# Adafruit_Feather_M0_Adalogger.net
KiCad netlist of a schematic drawn in EAGLE
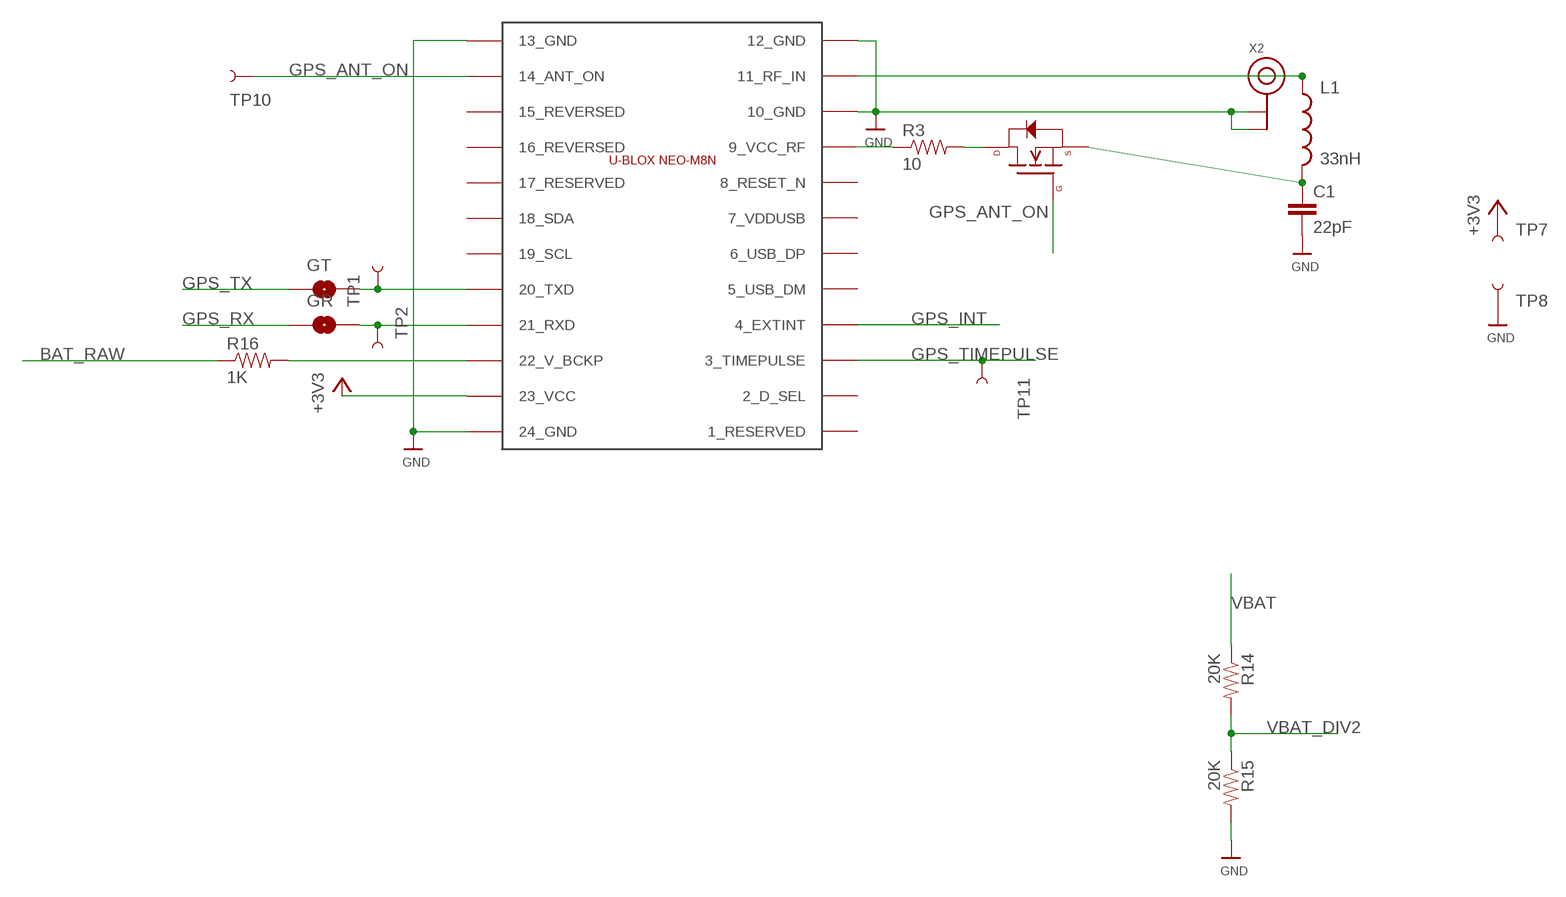
[diagram p0: schematic, sheet 1, part 1 of 2]
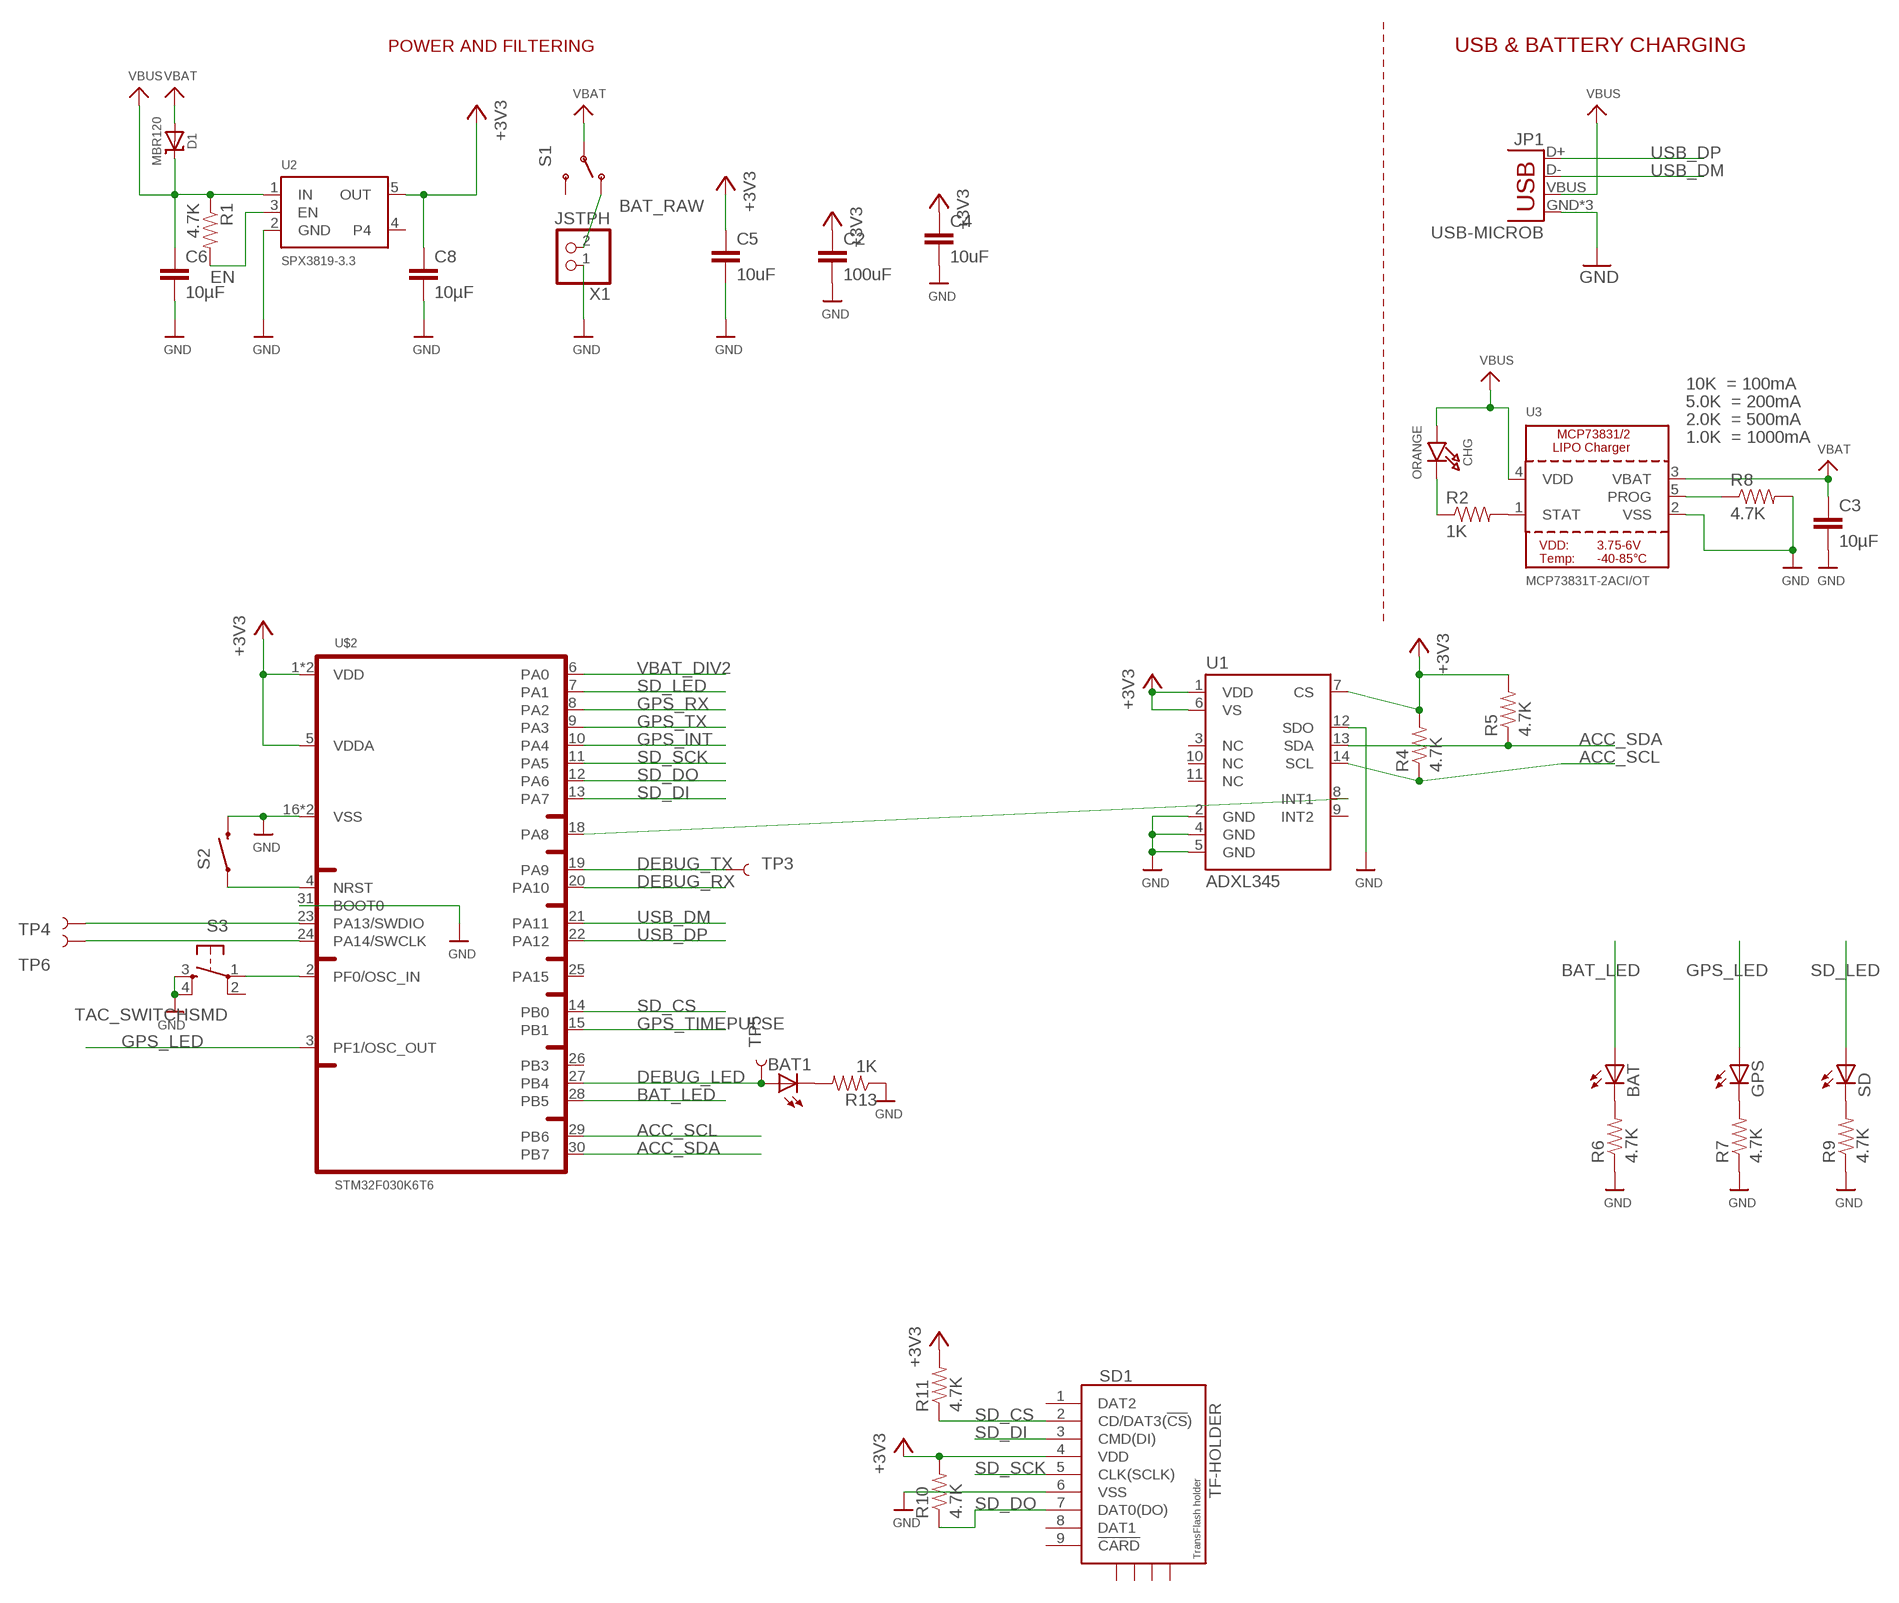
[diagram p1: schematic, sheet 1, part 2 of 2]

(export (version "E")
  (design (tool "Eeschema 10.0.6"))
  (components
    (comp (ref "BAT")
      (value "LEDCHIPLED_0805")
      (footprint "eagle-import:CHIPLED_0805")
      (libsource (lib "eagle-import") (part "LEDCHIPLED_0805"))
    )
    (comp (ref "BAT1")
      (value "LEDCHIPLED_0805")
      (footprint "eagle-import:CHIPLED_0805")
      (libsource (lib "eagle-import") (part "LEDCHIPLED_0805"))
    )
    (comp (ref "C1")
      (value "22pF")
      (footprint "eagle-import:0805")
      (libsource (lib "eagle-import") (part "CAP0805"))
    )
    (comp (ref "C2")
      (value "100uF")
      (footprint "eagle-import:1210")
      (libsource (lib "eagle-import") (part "100UF6.3V20%(1210)"))
    )
    (comp (ref "C3")
      (value "10µF")
      (footprint "eagle-import:0805")
      (libsource (lib "eagle-import") (part "CAP0805"))
    )
    (comp (ref "C4")
      (value "10uF")
      (footprint "eagle-import:0805")
      (libsource (lib "eagle-import") (part "CAP0805"))
    )
    (comp (ref "C5")
      (value "10uF")
      (footprint "eagle-import:0805")
      (libsource (lib "eagle-import") (part "CAP0805"))
    )
    (comp (ref "C6")
      (value "10µF")
      (footprint "eagle-import:0805")
      (libsource (lib "eagle-import") (part "CAP0805"))
    )
    (comp (ref "C8")
      (value "10µF")
      (footprint "eagle-import:0805")
      (libsource (lib "eagle-import") (part "CAP0805"))
    )
    (comp (ref "CHG")
      (value "ORANGE")
      (footprint "eagle-import:CHIPLED_0805_NOOUTLINE")
      (libsource (lib "eagle-import") (part "LED0805_NOOUTLINE"))
    )
    (comp (ref "D1")
      (value "MBR120")
      (footprint "eagle-import:SOD-123")
      (libsource (lib "eagle-import") (part "DIODE-SCHOTTKYSOD-123"))
    )
    (comp (ref "DEKU1")
      (value "UBLOX_NEO-M8N")
      (footprint "eagle-import:UBLOX_NEO-M8N")
      (libsource (lib "eagle-import") (part "UBLOX_NEO-M8N"))
    )
    (comp (ref "GPS")
      (value "LEDCHIPLED_0805")
      (footprint "eagle-import:CHIPLED_0805")
      (libsource (lib "eagle-import") (part "LEDCHIPLED_0805"))
    )
    (comp (ref "GR")
      (value "JUMPER-PAD-2-NO")
      (footprint "eagle-import:PAD-JUMPER-2-NO_NO_SILK")
      (libsource (lib "eagle-import") (part "JUMPER-PAD-2-NO"))
    )
    (comp (ref "GT")
      (value "JUMPER-PAD-2-NO")
      (footprint "eagle-import:PAD-JUMPER-2-NO_NO_SILK")
      (libsource (lib "eagle-import") (part "JUMPER-PAD-2-NO"))
    )
    (comp (ref "JP1")
      (value "USB-MICROB")
      (footprint "eagle-import:USB-MICROB")
      (libsource (lib "eagle-import") (part "USB-MICROB"))
    )
    (comp (ref "L1")
      (value "33nH")
      (footprint "eagle-import:0805")
      (libsource (lib "eagle-import") (part "INDUCTOR0805"))
    )
    (comp (ref "R1")
      (value "4.7K")
      (footprint "eagle-import:0805")
      (libsource (lib "eagle-import") (part "RESISTOR0805-RES"))
    )
    (comp (ref "R2")
      (value "1K")
      (footprint "eagle-import:0805")
      (libsource (lib "eagle-import") (part "RESISTOR0805-RES"))
    )
    (comp (ref "R3")
      (value "10")
      (footprint "eagle-import:0805")
      (libsource (lib "eagle-import") (part "RESISTOR0805-RES"))
    )
    (comp (ref "R4")
      (value "4.7K")
      (footprint "eagle-import:0805")
      (libsource (lib "eagle-import") (part "RESISTOR0805-RES"))
    )
    (comp (ref "R5")
      (value "4.7K")
      (footprint "eagle-import:0805")
      (libsource (lib "eagle-import") (part "RESISTOR0805-RES"))
    )
    (comp (ref "R6")
      (value "4.7K")
      (footprint "eagle-import:0805")
      (libsource (lib "eagle-import") (part "RESISTOR0805-RES"))
    )
    (comp (ref "R7")
      (value "4.7K")
      (footprint "eagle-import:0805")
      (libsource (lib "eagle-import") (part "RESISTOR0805-RES"))
    )
    (comp (ref "R8")
      (value "4.7K")
      (footprint "eagle-import:0805")
      (libsource (lib "eagle-import") (part "RESISTOR0805-RES"))
    )
    (comp (ref "R9")
      (value "4.7K")
      (footprint "eagle-import:0805")
      (libsource (lib "eagle-import") (part "RESISTOR0805-RES"))
    )
    (comp (ref "R10")
      (value "4.7K")
      (footprint "eagle-import:0805")
      (libsource (lib "eagle-import") (part "RESISTOR0805-RES"))
    )
    (comp (ref "R11")
      (value "4.7K")
      (footprint "eagle-import:0805")
      (libsource (lib "eagle-import") (part "RESISTOR0805-RES"))
    )
    (comp (ref "R13")
      (value "1K")
      (footprint "eagle-import:0805")
      (libsource (lib "eagle-import") (part "RESISTOR0805-RES"))
    )
    (comp (ref "R14")
      (value "20K")
      (footprint "eagle-import:0805")
      (libsource (lib "eagle-import") (part "RESISTOR0805-RES"))
    )
    (comp (ref "R15")
      (value "20K")
      (footprint "eagle-import:0805")
      (libsource (lib "eagle-import") (part "RESISTOR0805-RES"))
    )
    (comp (ref "R16")
      (value "1K")
      (footprint "eagle-import:0805")
      (libsource (lib "eagle-import") (part "RESISTOR0805-RES"))
    )
    (comp (ref "S1")
      (value "SWITCH-SPDT-SMD-A")
      (footprint "eagle-import:SWITCH-SPST-SMD-A")
      (libsource (lib "eagle-import") (part "SWITCH-SPDT-SMD-A"))
    )
    (comp (ref "S2")
      (value "SWITCH-MOMENTARY-2TURTLE")
      (footprint "eagle-import:KMR2")
      (libsource (lib "eagle-import") (part "SWITCH-MOMENTARY-2TURTLE"))
    )
    (comp (ref "S3")
      (value "TAC_SWITCHSMD")
      (footprint "eagle-import:TACTILE-SWITCH-SMD")
      (libsource (lib "eagle-import") (part "TAC_SWITCHSMD"))
    )
    (comp (ref "SD")
      (value "LEDCHIPLED_0805")
      (footprint "eagle-import:CHIPLED_0805")
      (libsource (lib "eagle-import") (part "LEDCHIPLED_0805"))
    )
    (comp (ref "SD1")
      (value "TF-HOLDER")
      (footprint "eagle-import:TF-PULL")
      (libsource (lib "eagle-import") (part "TF-HOLDER"))
    )
    (comp (ref "TP1")
      (value "TEST-POINT3X5")
      (footprint "eagle-import:PAD.03X.05")
      (libsource (lib "eagle-import") (part "TEST-POINT3X5"))
    )
    (comp (ref "TP2")
      (value "TEST-POINT3X5")
      (footprint "eagle-import:PAD.03X.05")
      (libsource (lib "eagle-import") (part "TEST-POINT3X5"))
    )
    (comp (ref "TP3")
      (value "TEST-POINT3X5")
      (footprint "eagle-import:PAD.03X.05")
      (libsource (lib "eagle-import") (part "TEST-POINT3X5"))
    )
    (comp (ref "TP4")
      (value "TEST-POINT3X5")
      (footprint "eagle-import:PAD.03X.05")
      (libsource (lib "eagle-import") (part "TEST-POINT3X5"))
    )
    (comp (ref "TP5")
      (value "TEST-POINT3X5")
      (footprint "eagle-import:PAD.03X.05")
      (libsource (lib "eagle-import") (part "TEST-POINT3X5"))
    )
    (comp (ref "TP6")
      (value "TEST-POINT3X5")
      (footprint "eagle-import:PAD.03X.05")
      (libsource (lib "eagle-import") (part "TEST-POINT3X5"))
    )
    (comp (ref "TP7")
      (value "TEST-POINT3X5")
      (footprint "eagle-import:PAD.03X.05")
      (libsource (lib "eagle-import") (part "TEST-POINT3X5"))
    )
    (comp (ref "TP8")
      (value "TEST-POINT3X5")
      (footprint "eagle-import:PAD.03X.05")
      (libsource (lib "eagle-import") (part "TEST-POINT3X5"))
    )
    (comp (ref "TP10")
      (value "TEST-POINT3X5")
      (footprint "eagle-import:PAD.03X.05")
      (libsource (lib "eagle-import") (part "TEST-POINT3X5"))
    )
    (comp (ref "TP11")
      (value "TEST-POINT3X5")
      (footprint "eagle-import:PAD.03X.05")
      (libsource (lib "eagle-import") (part "TEST-POINT3X5"))
    )
    (comp (ref "U$2")
      (value "STM32F030K6T6")
      (footprint "eagle-import:TQFP32-08")
      (libsource (lib "eagle-import") (part "STM32F030K6T6"))
    )
    (comp (ref "U$24")
      (value "N-CHANNEL-MOSFET-BSS138")
      (footprint "eagle-import:SOT23-3")
      (libsource (lib "eagle-import") (part "N-CHANNEL-MOSFET-BSS138"))
    )
    (comp (ref "U1")
      (value "ADXL345")
      (footprint "eagle-import:LGA14")
      (libsource (lib "eagle-import") (part "ADXL345"))
    )
    (comp (ref "U2")
      (value "SPX3819-3.3")
      (footprint "eagle-import:SOT23-5")
      (libsource (lib "eagle-import") (part "VREG_SOT23-5"))
    )
    (comp (ref "U3")
      (value "MCP73831T-2ACI/OT")
      (footprint "eagle-import:SOT23-5")
      (libsource (lib "eagle-import") (part "MCP73831/2"))
    )
    (comp (ref "X1")
      (value "JSTPH")
      (footprint "eagle-import:JSTPH2")
      (libsource (lib "eagle-import") (part "CON_JST_PH_2PIN"))
    )
    (comp (ref "X2")
      (value "ANTENNA_U.FL")
      (footprint "eagle-import:U.FL")
      (libsource (lib "eagle-import") (part "ANTENNA_U.FL"))
    )
  )
  (nets
    (net (code "1") (name "+3V3") (class "Default")
      (node (ref "C2") (pin "1") (pinfunction "1_1") (pintype "passive"))
      (node (ref "C4") (pin "1") (pinfunction "1_1") (pintype "passive"))
      (node (ref "C5") (pin "1") (pinfunction "1_1") (pintype "passive"))
      (node (ref "C8") (pin "1") (pinfunction "1_1") (pintype "passive"))
      (node (ref "DEKU1") (pin "23_VCC") (pinfunction "23_VCC_23_VCC") (pintype "bidirectional"))
      (node (ref "R10") (pin "2") (pinfunction "2_2") (pintype "passive"))
      (node (ref "R11") (pin "2") (pinfunction "2_2") (pintype "passive"))
      (node (ref "R4") (pin "2") (pinfunction "2_2") (pintype "passive"))
      (node (ref "R5") (pin "2") (pinfunction "2_2") (pintype "passive"))
      (node (ref "SD1") (pin "4") (pinfunction "VDD_4") (pintype "power_in"))
      (node (ref "TP7") (pin "P$1") (pinfunction "1_P$1") (pintype "bidirectional"))
      (node (ref "U$2") (pin "1") (pinfunction "VDD_1") (pintype "bidirectional"))
      (node (ref "U$2") (pin "17") (pinfunction "VDD_17") (pintype "bidirectional"))
      (node (ref "U$2") (pin "5") (pinfunction "VDDA_5") (pintype "bidirectional"))
      (node (ref "U1") (pin "1") (pinfunction "VDD_1") (pintype "bidirectional"))
      (node (ref "U1") (pin "6") (pinfunction "VS_6") (pintype "bidirectional"))
      (node (ref "U1") (pin "7") (pinfunction "CS_7") (pintype "bidirectional"))
      (node (ref "U2") (pin "5") (pinfunction "OUT_5") (pintype "power_in"))
    )
    (net (code "2") (name "/ACC_SCL") (class "Default")
      (node (ref "R4") (pin "1") (pinfunction "1_1") (pintype "passive"))
      (node (ref "U$2") (pin "29") (pinfunction "PB6_29") (pintype "bidirectional"))
      (node (ref "U1") (pin "14") (pinfunction "SCL_14") (pintype "bidirectional"))
    )
    (net (code "3") (name "/ACC_SDA") (class "Default")
      (node (ref "R5") (pin "1") (pinfunction "1_1") (pintype "passive"))
      (node (ref "U$2") (pin "30") (pinfunction "PB7_30") (pintype "bidirectional"))
      (node (ref "U1") (pin "13") (pinfunction "SDA_13") (pintype "bidirectional"))
    )
    (net (code "4") (name "/BAT_LED") (class "Default")
      (node (ref "BAT") (pin "A") (pinfunction "A_A") (pintype "passive"))
      (node (ref "U$2") (pin "28") (pinfunction "PB5_28") (pintype "bidirectional"))
    )
    (net (code "5") (name "/BAT_RAW") (class "Default")
      (node (ref "R16") (pin "1") (pinfunction "1_1") (pintype "passive"))
      (node (ref "S1") (pin "1") (pinfunction "O_1") (pintype "passive"))
      (node (ref "X1") (pin "2") (pinfunction "2_2") (pintype "passive"))
    )
    (net (code "6") (name "/DEBUG_LED") (class "Default")
      (node (ref "BAT1") (pin "A") (pinfunction "A_A") (pintype "passive"))
      (node (ref "TP5") (pin "P$1") (pinfunction "1_P$1") (pintype "bidirectional"))
      (node (ref "U$2") (pin "27") (pinfunction "PB4_27") (pintype "bidirectional"))
    )
    (net (code "7") (name "/DEBUG_RX") (class "Default")
      (node (ref "U$2") (pin "20") (pinfunction "PA10_20") (pintype "bidirectional"))
    )
    (net (code "8") (name "/DEBUG_TX") (class "Default")
      (node (ref "TP3") (pin "P$1") (pinfunction "1_P$1") (pintype "bidirectional"))
      (node (ref "U$2") (pin "19") (pinfunction "PA9_19") (pintype "bidirectional"))
    )
    (net (code "9") (name "/EN") (class "Default")
      (node (ref "R1") (pin "2") (pinfunction "2_2") (pintype "passive"))
      (node (ref "U2") (pin "3") (pinfunction "EN_3") (pintype "input"))
    )
    (net (code "10") (name "/GPS_ANT_ON") (class "Default")
      (node (ref "DEKU1") (pin "14_ANT_ON") (pinfunction "14_ANT_ON_14_ANT_ON") (pintype "bidirectional"))
      (node (ref "TP10") (pin "P$1") (pinfunction "1_P$1") (pintype "bidirectional"))
      (node (ref "U$24") (pin "1") (pinfunction "G_1") (pintype "passive"))
    )
    (net (code "11") (name "/GPS_INT") (class "Default")
      (node (ref "DEKU1") (pin "4_EXTINT") (pinfunction "4_EXTINT_4_EXTINT") (pintype "bidirectional"))
      (node (ref "U$2") (pin "10") (pinfunction "PA4_10") (pintype "bidirectional"))
    )
    (net (code "12") (name "/GPS_LED") (class "Default")
      (node (ref "GPS") (pin "A") (pinfunction "A_A") (pintype "passive"))
      (node (ref "U$2") (pin "3") (pinfunction "PF1/OSC_OUT_3") (pintype "bidirectional"))
    )
    (net (code "13") (name "/GPS_RX") (class "Default")
      (node (ref "GR") (pin "1") (pinfunction "1_1") (pintype "passive"))
      (node (ref "U$2") (pin "8") (pinfunction "PA2_8") (pintype "bidirectional"))
    )
    (net (code "14") (name "/GPS_TIMEPULSE") (class "Default")
      (node (ref "DEKU1") (pin "3_TIMEPULSE") (pinfunction "3_TIMEPULSE_3_TIMEPULSE") (pintype "bidirectional"))
      (node (ref "TP11") (pin "P$1") (pinfunction "1_P$1") (pintype "bidirectional"))
      (node (ref "U$2") (pin "15") (pinfunction "PB1_15") (pintype "bidirectional"))
    )
    (net (code "15") (name "/GPS_TX") (class "Default")
      (node (ref "GT") (pin "1") (pinfunction "1_1") (pintype "passive"))
      (node (ref "U$2") (pin "9") (pinfunction "PA3_9") (pintype "bidirectional"))
    )
    (net (code "16") (name "/SD_CS") (class "Default")
      (node (ref "R11") (pin "1") (pinfunction "1_1") (pintype "passive"))
      (node (ref "SD1") (pin "2") (pinfunction "CD/DAT3(~{CS})_2") (pintype "bidirectional"))
      (node (ref "U$2") (pin "14") (pinfunction "PB0_14") (pintype "bidirectional"))
    )
    (net (code "17") (name "/SD_DI") (class "Default")
      (node (ref "SD1") (pin "3") (pinfunction "CMD(DI)_3") (pintype "bidirectional"))
      (node (ref "U$2") (pin "13") (pinfunction "PA7_13") (pintype "bidirectional"))
    )
    (net (code "18") (name "/SD_DO") (class "Default")
      (node (ref "R10") (pin "1") (pinfunction "1_1") (pintype "passive"))
      (node (ref "SD1") (pin "7") (pinfunction "DAT0(DO)_7") (pintype "bidirectional"))
      (node (ref "U$2") (pin "12") (pinfunction "PA6_12") (pintype "bidirectional"))
    )
    (net (code "19") (name "/SD_LED") (class "Default")
      (node (ref "SD") (pin "A") (pinfunction "A_A") (pintype "passive"))
      (node (ref "U$2") (pin "7") (pinfunction "PA1_7") (pintype "bidirectional"))
    )
    (net (code "20") (name "/SD_SCK") (class "Default")
      (node (ref "SD1") (pin "5") (pinfunction "CLK(SCLK)_5") (pintype "input"))
      (node (ref "U$2") (pin "11") (pinfunction "PA5_11") (pintype "bidirectional"))
    )
    (net (code "21") (name "/USB_DM") (class "Default")
      (node (ref "JP1") (pin "D-") (pinfunction "D-_D-") (pintype "bidirectional"))
      (node (ref "U$2") (pin "21") (pinfunction "PA11_21") (pintype "bidirectional"))
    )
    (net (code "22") (name "/USB_DP") (class "Default")
      (node (ref "JP1") (pin "D+") (pinfunction "D+_D+") (pintype "bidirectional"))
      (node (ref "U$2") (pin "22") (pinfunction "PA12_22") (pintype "bidirectional"))
    )
    (net (code "23") (name "/VBAT_DIV2") (class "Default")
      (node (ref "R14") (pin "2") (pinfunction "2_2") (pintype "passive"))
      (node (ref "R15") (pin "1") (pinfunction "1_1") (pintype "passive"))
      (node (ref "U$2") (pin "6") (pinfunction "PA0_6") (pintype "bidirectional"))
    )
    (net (code "24") (name "GND") (class "Default")
      (node (ref "C1") (pin "2") (pinfunction "2_2") (pintype "passive"))
      (node (ref "C2") (pin "2") (pinfunction "2_2") (pintype "passive"))
      (node (ref "C3") (pin "2") (pinfunction "2_2") (pintype "passive"))
      (node (ref "C4") (pin "2") (pinfunction "2_2") (pintype "passive"))
      (node (ref "C5") (pin "2") (pinfunction "2_2") (pintype "passive"))
      (node (ref "C6") (pin "2") (pinfunction "2_2") (pintype "passive"))
      (node (ref "C8") (pin "2") (pinfunction "2_2") (pintype "passive"))
      (node (ref "DEKU1") (pin "10_GND") (pinfunction "10_GND_10_GND") (pintype "bidirectional"))
      (node (ref "DEKU1") (pin "12_GND") (pinfunction "12_GND_12_GND") (pintype "bidirectional"))
      (node (ref "DEKU1") (pin "13_GND") (pinfunction "13_GND_13_GND") (pintype "bidirectional"))
      (node (ref "DEKU1") (pin "24_GND") (pinfunction "24_GND_24_GND") (pintype "bidirectional"))
      (node (ref "JP1") (pin "GND") (pinfunction "GND_GND") (pintype "bidirectional"))
      (node (ref "JP1") (pin "MT1") (pinfunction "GND_MT1") (pintype "bidirectional"))
      (node (ref "JP1") (pin "MT2") (pinfunction "GND_MT2") (pintype "bidirectional"))
      (node (ref "R13") (pin "1") (pinfunction "1_1") (pintype "passive"))
      (node (ref "R15") (pin "2") (pinfunction "2_2") (pintype "passive"))
      (node (ref "R6") (pin "1") (pinfunction "1_1") (pintype "passive"))
      (node (ref "R7") (pin "1") (pinfunction "1_1") (pintype "passive"))
      (node (ref "R8") (pin "2") (pinfunction "2_2") (pintype "passive"))
      (node (ref "R9") (pin "1") (pinfunction "1_1") (pintype "passive"))
      (node (ref "S2") (pin "3") (pinfunction "2_3") (pintype "passive"))
      (node (ref "S3") (pin "3") (pinfunction "3_3") (pintype "passive"))
      (node (ref "S3") (pin "4") (pinfunction "4_4") (pintype "passive"))
      (node (ref "SD1") (pin "6") (pinfunction "VSS_6") (pintype "power_in"))
      (node (ref "TP8") (pin "P$1") (pinfunction "1_P$1") (pintype "bidirectional"))
      (node (ref "U$2") (pin "16") (pinfunction "VSS_16") (pintype "bidirectional"))
      (node (ref "U$2") (pin "31") (pinfunction "BOOT0_31") (pintype "bidirectional"))
      (node (ref "U$2") (pin "32") (pinfunction "VSS_32") (pintype "bidirectional"))
      (node (ref "U1") (pin "12") (pinfunction "SDO_12") (pintype "bidirectional"))
      (node (ref "U1") (pin "2") (pinfunction "GND_2") (pintype "bidirectional"))
      (node (ref "U1") (pin "4") (pinfunction "GND_4") (pintype "bidirectional"))
      (node (ref "U1") (pin "5") (pinfunction "GND_5") (pintype "bidirectional"))
      (node (ref "U2") (pin "2") (pinfunction "GND_2") (pintype "power_in"))
      (node (ref "U3") (pin "2") (pinfunction "VSS_2") (pintype "power_in"))
      (node (ref "X1") (pin "1") (pinfunction "1_1") (pintype "passive"))
      (node (ref "X2") (pin "1") (pinfunction "GND_1") (pintype "passive"))
      (node (ref "X2") (pin "2") (pinfunction "GND_2") (pintype "passive"))
    )
    (net (code "25") (name "Net-(BAT-PadC)") (class "Default")
      (node (ref "BAT") (pin "C") (pinfunction "C_C") (pintype "passive"))
      (node (ref "R6") (pin "2") (pinfunction "2_2") (pintype "passive"))
    )
    (net (code "26") (name "Net-(BAT1-PadC)") (class "Default")
      (node (ref "BAT1") (pin "C") (pinfunction "C_C") (pintype "passive"))
      (node (ref "R13") (pin "2") (pinfunction "2_2") (pintype "passive"))
    )
    (net (code "27") (name "Net-(CHG-PadC)") (class "Default")
      (node (ref "CHG") (pin "C") (pinfunction "C_C") (pintype "passive"))
      (node (ref "R2") (pin "1") (pinfunction "1_1") (pintype "passive"))
    )
    (net (code "28") (name "Net-(DEKU1-Pad9_VCC_RF)") (class "Default")
      (node (ref "DEKU1") (pin "9_VCC_RF") (pinfunction "9_VCC_RF_9_VCC_RF") (pintype "bidirectional"))
      (node (ref "R3") (pin "1") (pinfunction "1_1") (pintype "passive"))
    )
    (net (code "29") (name "Net-(DEKU1-Pad22_V_BCKP)") (class "Default")
      (node (ref "DEKU1") (pin "22_V_BCKP") (pinfunction "22_V_BCKP_22_V_BCKP") (pintype "bidirectional"))
      (node (ref "R16") (pin "2") (pinfunction "2_2") (pintype "passive"))
    )
    (net (code "30") (name "Net-(GPS-PadC)") (class "Default")
      (node (ref "GPS") (pin "C") (pinfunction "C_C") (pintype "passive"))
      (node (ref "R7") (pin "2") (pinfunction "2_2") (pintype "passive"))
    )
    (net (code "31") (name "Net-(R9-Pad2)") (class "Default")
      (node (ref "R9") (pin "2") (pinfunction "2_2") (pintype "passive"))
      (node (ref "SD") (pin "C") (pinfunction "C_C") (pintype "passive"))
    )
    (net (code "32") (name "Net-(TP1-1)") (class "Default")
      (node (ref "DEKU1") (pin "20_TXD") (pinfunction "20_TXD_20_TXD") (pintype "bidirectional"))
      (node (ref "GT") (pin "2") (pinfunction "2_2") (pintype "passive"))
      (node (ref "TP1") (pin "P$1") (pinfunction "1_P$1") (pintype "bidirectional"))
    )
    (net (code "33") (name "Net-(TP2-1)") (class "Default")
      (node (ref "DEKU1") (pin "21_RXD") (pinfunction "21_RXD_21_RXD") (pintype "bidirectional"))
      (node (ref "GR") (pin "2") (pinfunction "2_2") (pintype "passive"))
      (node (ref "TP2") (pin "P$1") (pinfunction "1_P$1") (pintype "bidirectional"))
    )
    (net (code "34") (name "Net-(TP4-1)") (class "Default")
      (node (ref "TP4") (pin "P$1") (pinfunction "1_P$1") (pintype "bidirectional"))
      (node (ref "U$2") (pin "23") (pinfunction "PA13/SWDIO_23") (pintype "bidirectional"))
    )
    (net (code "35") (name "Net-(TP6-1)") (class "Default")
      (node (ref "TP6") (pin "P$1") (pinfunction "1_P$1") (pintype "bidirectional"))
      (node (ref "U$2") (pin "24") (pinfunction "PA14/SWCLK_24") (pintype "bidirectional"))
    )
    (net (code "36") (name "Net-(U$2-NRST)") (class "Default")
      (node (ref "S2") (pin "1") (pinfunction "1_1") (pintype "passive"))
      (node (ref "U$2") (pin "4") (pinfunction "NRST_4") (pintype "bidirectional"))
    )
    (net (code "37") (name "Net-(U$2-PA8)") (class "Default")
      (node (ref "U$2") (pin "18") (pinfunction "PA8_18") (pintype "bidirectional"))
      (node (ref "U1") (pin "8") (pinfunction "INT1_8") (pintype "bidirectional"))
    )
    (net (code "38") (name "Net-(U$2-PF0{slash}OSC_IN)") (class "Default")
      (node (ref "S3") (pin "1") (pinfunction "1_1") (pintype "passive"))
      (node (ref "U$2") (pin "2") (pinfunction "PF0/OSC_IN_2") (pintype "bidirectional"))
    )
    (net (code "39") (name "Net-(U$24-D)") (class "Default")
      (node (ref "R3") (pin "2") (pinfunction "2_2") (pintype "passive"))
      (node (ref "U$24") (pin "3") (pinfunction "D_3") (pintype "passive"))
    )
    (net (code "40") (name "Net-(U$24-S)") (class "Default")
      (node (ref "C1") (pin "1") (pinfunction "1_1") (pintype "passive"))
      (node (ref "L1") (pin "2") (pinfunction "2_2") (pintype "passive"))
      (node (ref "U$24") (pin "2") (pinfunction "S_2") (pintype "passive"))
    )
    (net (code "41") (name "Net-(U3-PROG)") (class "Default")
      (node (ref "R8") (pin "1") (pinfunction "1_1") (pintype "passive"))
      (node (ref "U3") (pin "5") (pinfunction "PROG_5") (pintype "input"))
    )
    (net (code "42") (name "Net-(U3-STAT)") (class "Default")
      (node (ref "R2") (pin "2") (pinfunction "2_2") (pintype "passive"))
      (node (ref "U3") (pin "1") (pinfunction "STAT_1") (pintype "output"))
    )
    (net (code "43") (name "Net-(X2-SIGNAL)") (class "Default")
      (node (ref "DEKU1") (pin "11_RF_IN") (pinfunction "11_RF_IN_11_RF_IN") (pintype "bidirectional"))
      (node (ref "L1") (pin "1") (pinfunction "1_1") (pintype "passive"))
      (node (ref "X2") (pin "3") (pinfunction "SIGNAL_3") (pintype "passive"))
    )
    (net (code "44") (name "VBAT") (class "Default")
      (node (ref "C3") (pin "1") (pinfunction "1_1") (pintype "passive"))
      (node (ref "D1") (pin "A") (pinfunction "A_A") (pintype "passive"))
      (node (ref "R14") (pin "1") (pinfunction "1_1") (pintype "passive"))
      (node (ref "S1") (pin "2") (pinfunction "P_2") (pintype "passive"))
      (node (ref "U3") (pin "3") (pinfunction "VBAT_3") (pintype "power_in"))
    )
    (net (code "45") (name "VBUS") (class "Default")
      (node (ref "C6") (pin "1") (pinfunction "1_1") (pintype "passive"))
      (node (ref "CHG") (pin "A") (pinfunction "A_A") (pintype "passive"))
      (node (ref "D1") (pin "C") (pinfunction "C_C") (pintype "passive"))
      (node (ref "JP1") (pin "VBUS") (pinfunction "VBUS_VBUS") (pintype "bidirectional"))
      (node (ref "R1") (pin "1") (pinfunction "1_1") (pintype "passive"))
      (node (ref "U2") (pin "1") (pinfunction "IN_1") (pintype "power_in"))
      (node (ref "U3") (pin "4") (pinfunction "VDD_4") (pintype "power_in"))
    )
    (net (code "46") (name "unconnected-(DEKU1-Pad1_RESERVED)") (class "Default")
      (node (ref "DEKU1") (pin "1_RESERVED") (pinfunction "1_RESERVED_1_RESERVED") (pintype "bidirectional"))
    )
    (net (code "47") (name "unconnected-(DEKU1-Pad2_D_SEL)") (class "Default")
      (node (ref "DEKU1") (pin "2_D_SEL") (pinfunction "2_D_SEL_2_D_SEL") (pintype "bidirectional"))
    )
    (net (code "48") (name "unconnected-(DEKU1-Pad5_USB_DM)") (class "Default")
      (node (ref "DEKU1") (pin "5_USB_DM") (pinfunction "5_USB_DM_5_USB_DM") (pintype "bidirectional"))
    )
    (net (code "49") (name "unconnected-(DEKU1-Pad6_USB_DP)") (class "Default")
      (node (ref "DEKU1") (pin "6_USB_DP") (pinfunction "6_USB_DP_6_USB_DP") (pintype "bidirectional"))
    )
    (net (code "50") (name "unconnected-(DEKU1-Pad7_VDDUSB)") (class "Default")
      (node (ref "DEKU1") (pin "7_VDDUSB") (pinfunction "7_VDDUSB_7_VDDUSB") (pintype "bidirectional"))
    )
    (net (code "51") (name "unconnected-(DEKU1-Pad8_RESET_N)") (class "Default")
      (node (ref "DEKU1") (pin "8_RESET_N") (pinfunction "8_RESET_N_8_RESET_N") (pintype "bidirectional"))
    )
    (net (code "52") (name "unconnected-(DEKU1-Pad15_REVERSED)") (class "Default")
      (node (ref "DEKU1") (pin "15_REVERSED") (pinfunction "15_REVERSED_15_REVERSED") (pintype "bidirectional"))
    )
    (net (code "53") (name "unconnected-(DEKU1-Pad16_REVERSED)") (class "Default")
      (node (ref "DEKU1") (pin "16_REVERSED") (pinfunction "16_REVERSED_16_REVERSED") (pintype "bidirectional"))
    )
    (net (code "54") (name "unconnected-(DEKU1-Pad17_RESERVED)") (class "Default")
      (node (ref "DEKU1") (pin "17_RESERVED") (pinfunction "17_RESERVED_17_RESERVED") (pintype "bidirectional"))
    )
    (net (code "55") (name "unconnected-(DEKU1-Pad18_SDA)") (class "Default")
      (node (ref "DEKU1") (pin "18_SDA") (pinfunction "18_SDA_18_SDA") (pintype "bidirectional"))
    )
    (net (code "56") (name "unconnected-(DEKU1-Pad19_SCL)") (class "Default")
      (node (ref "DEKU1") (pin "19_SCL") (pinfunction "19_SCL_19_SCL") (pintype "bidirectional"))
    )
    (net (code "57") (name "unconnected-(S1-S-Pad3)") (class "Default")
      (node (ref "S1") (pin "3") (pinfunction "S_3") (pintype "passive"))
    )
    (net (code "58") (name "unconnected-(S3-Pad2)") (class "Default")
      (node (ref "S3") (pin "2") (pinfunction "2_2") (pintype "passive"))
    )
    (net (code "59") (name "unconnected-(SD1-DAT1-Pad8)") (class "Default")
      (node (ref "SD1") (pin "8") (pinfunction "DAT1_8") (pintype "bidirectional"))
    )
    (net (code "60") (name "unconnected-(SD1-DAT2-Pad1)") (class "Default")
      (node (ref "SD1") (pin "1") (pinfunction "DAT2_1") (pintype "bidirectional"))
    )
    (net (code "61") (name "unconnected-(SD1-PadS1)") (class "Default")
      (node (ref "SD1") (pin "S1") (pinfunction "S1_S1") (pintype "passive"))
    )
    (net (code "62") (name "unconnected-(SD1-PadS2)") (class "Default")
      (node (ref "SD1") (pin "S2") (pinfunction "S2_S2") (pintype "passive"))
    )
    (net (code "63") (name "unconnected-(SD1-PadS3)") (class "Default")
      (node (ref "SD1") (pin "S3") (pinfunction "S3_S3") (pintype "passive"))
    )
    (net (code "64") (name "unconnected-(SD1-PadS4)") (class "Default")
      (node (ref "SD1") (pin "S4") (pinfunction "S4_S4") (pintype "passive"))
    )
    (net (code "65") (name "unconnected-(SD1-~{CARD}-Pad9)") (class "Default")
      (node (ref "SD1") (pin "9") (pinfunction "~{CARD}_9") (pintype "passive"))
    )
    (net (code "66") (name "unconnected-(U$2-PA15-Pad25)") (class "Default")
      (node (ref "U$2") (pin "25") (pinfunction "PA15_25") (pintype "bidirectional"))
    )
    (net (code "67") (name "unconnected-(U$2-PB3-Pad26)") (class "Default")
      (node (ref "U$2") (pin "26") (pinfunction "PB3_26") (pintype "bidirectional"))
    )
    (net (code "68") (name "unconnected-(U1-INT2-Pad9)") (class "Default")
      (node (ref "U1") (pin "9") (pinfunction "INT2_9") (pintype "bidirectional"))
    )
    (net (code "69") (name "unconnected-(U1-NC-Pad3)") (class "Default")
      (node (ref "U1") (pin "3") (pinfunction "NC_3") (pintype "bidirectional"))
    )
    (net (code "70") (name "unconnected-(U1-NC-Pad10)") (class "Default")
      (node (ref "U1") (pin "10") (pinfunction "NC_10") (pintype "bidirectional"))
    )
    (net (code "71") (name "unconnected-(U1-NC-Pad11)") (class "Default")
      (node (ref "U1") (pin "11") (pinfunction "NC_11") (pintype "bidirectional"))
    )
    (net (code "72") (name "unconnected-(U2-P4-Pad4)") (class "Default")
      (node (ref "U2") (pin "4") (pinfunction "P4_4") (pintype "bidirectional"))
    )
  )
)
